# I2C_ISO.net
KiCad netlist of a schematic drawn in Altium Designer
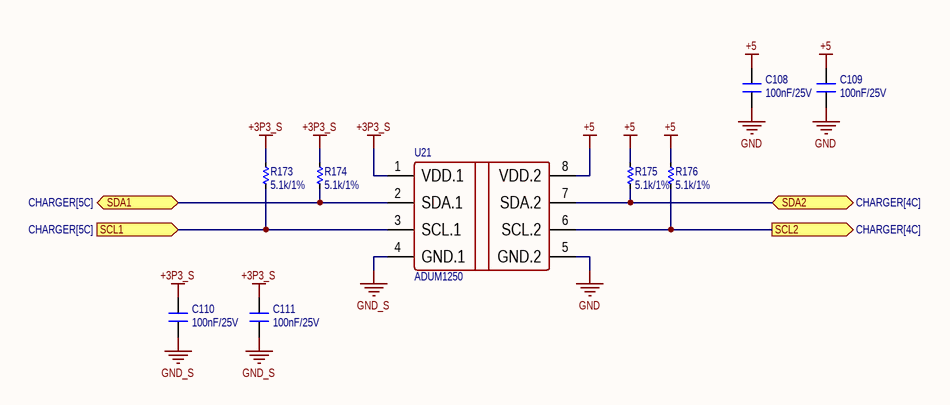
[diagram p0: I2C_ISO.SchDoc]

(export (version "E")
  (design (tool "Eeschema 10.0.6"))
  (components
    (comp (ref "C108")
      (value "100nF/25V")
      (footprint "CN-SMD-0603")
      (description "CAP CER 0.1UF 25V X7R 0603")
      (libsource (lib "Library") (part "CN"))
    )
    (comp (ref "C109")
      (value "100nF/25V")
      (footprint "CN-SMD-0603")
      (description "CAP CER 0.1UF 25V X7R 0603")
      (libsource (lib "Library") (part "CN"))
    )
    (comp (ref "C110")
      (value "100nF/25V")
      (footprint "CN-SMD-0603")
      (description "CAP CER 0.1UF 25V X7R 0603")
      (libsource (lib "Library") (part "CN"))
    )
    (comp (ref "C111")
      (value "100nF/25V")
      (footprint "CN-SMD-0603")
      (description "CAP CER 0.1UF 25V X7R 0603")
      (libsource (lib "Library") (part "CN"))
    )
    (comp (ref "R173")
      (value "5.1k/1%")
      (footprint "RES-SMD-0603")
      (description "RES SMD 5.1K OHM 1% 1/10W 0603")
      (fields
        (field (name "MANUFACTURER") "Generic Components")
        (field (name "PUBLISHER") "Altium Hobart Technology Centre")
      )
      (libsource (lib "Library") (part "Res-SMD"))
    )
    (comp (ref "R174")
      (value "5.1k/1%")
      (footprint "RES-SMD-0603")
      (description "RES SMD 5.1K OHM 1% 1/10W 0603")
      (fields
        (field (name "MANUFACTURER") "Generic Components")
        (field (name "PUBLISHER") "Altium Hobart Technology Centre")
      )
      (libsource (lib "Library") (part "Res-SMD"))
    )
    (comp (ref "R175")
      (value "5.1k/1%")
      (footprint "RES-SMD-0603")
      (description "RES SMD 5.1K OHM 1% 1/10W 0603")
      (fields
        (field (name "MANUFACTURER") "Generic Components")
        (field (name "PUBLISHER") "Altium Hobart Technology Centre")
      )
      (libsource (lib "Library") (part "Res-SMD"))
    )
    (comp (ref "R176")
      (value "5.1k/1%")
      (footprint "RES-SMD-0603")
      (description "RES SMD 5.1K OHM 1% 1/10W 0603")
      (fields
        (field (name "MANUFACTURER") "Generic Components")
        (field (name "PUBLISHER") "Altium Hobart Technology Centre")
      )
      (libsource (lib "Library") (part "Res-SMD"))
    )
    (comp (ref "U21")
      (value "ADUM1250")
      (footprint "SO8")
      (description "DGTL ISOLTR 2.5KV 2CH I2C 8-SOIC")
      (libsource (lib "Library") (part "ADUM1250"))
    )
  )
  (nets
    (net (code "1") (name "+3P3_S") (class "Default")
      (node (ref "C110") (pin "1") (pinfunction "1_1") (pintype "passive"))
      (node (ref "C111") (pin "1") (pinfunction "1_1") (pintype "passive"))
      (node (ref "R173") (pin "1") (pinfunction "1_1") (pintype "passive"))
      (node (ref "R174") (pin "1") (pinfunction "1_1") (pintype "passive"))
      (node (ref "U21") (pin "1") (pinfunction "VDD.1_1") (pintype "passive"))
    )
    (net (code "2") (name "+5") (class "Default")
      (node (ref "C108") (pin "1") (pinfunction "1_1") (pintype "passive"))
      (node (ref "C109") (pin "1") (pinfunction "1_1") (pintype "passive"))
      (node (ref "R175") (pin "1") (pinfunction "1_1") (pintype "passive"))
      (node (ref "R176") (pin "1") (pinfunction "1_1") (pintype "passive"))
      (node (ref "U21") (pin "8") (pinfunction "VDD.2_8") (pintype "passive"))
    )
    (net (code "3") (name "/SCL1") (class "Default")
      (node (ref "R173") (pin "2") (pinfunction "2_2") (pintype "passive"))
      (node (ref "U21") (pin "3") (pinfunction "SCL.1_3") (pintype "passive"))
    )
    (net (code "4") (name "/SCL2") (class "Default")
      (node (ref "R176") (pin "2") (pinfunction "2_2") (pintype "passive"))
      (node (ref "U21") (pin "6") (pinfunction "SCL.2_6") (pintype "passive"))
    )
    (net (code "5") (name "/SDA1") (class "Default")
      (node (ref "R174") (pin "2") (pinfunction "2_2") (pintype "passive"))
      (node (ref "U21") (pin "2") (pinfunction "SDA.1_2") (pintype "passive"))
    )
    (net (code "6") (name "/SDA2") (class "Default")
      (node (ref "R175") (pin "2") (pinfunction "2_2") (pintype "passive"))
      (node (ref "U21") (pin "7") (pinfunction "SDA.2_7") (pintype "passive"))
    )
    (net (code "7") (name "GND") (class "Default")
      (node (ref "C108") (pin "2") (pinfunction "2_2") (pintype "passive"))
      (node (ref "C109") (pin "2") (pinfunction "2_2") (pintype "passive"))
      (node (ref "U21") (pin "5") (pinfunction "GND.2_5") (pintype "passive"))
    )
    (net (code "8") (name "GND_S") (class "Default")
      (node (ref "C110") (pin "2") (pinfunction "2_2") (pintype "passive"))
      (node (ref "C111") (pin "2") (pinfunction "2_2") (pintype "passive"))
      (node (ref "U21") (pin "4") (pinfunction "GND.1_4") (pintype "passive"))
    )
  )
)
